# DC_DC_self_powerd.net
KiCad netlist of a schematic drawn in EAGLE
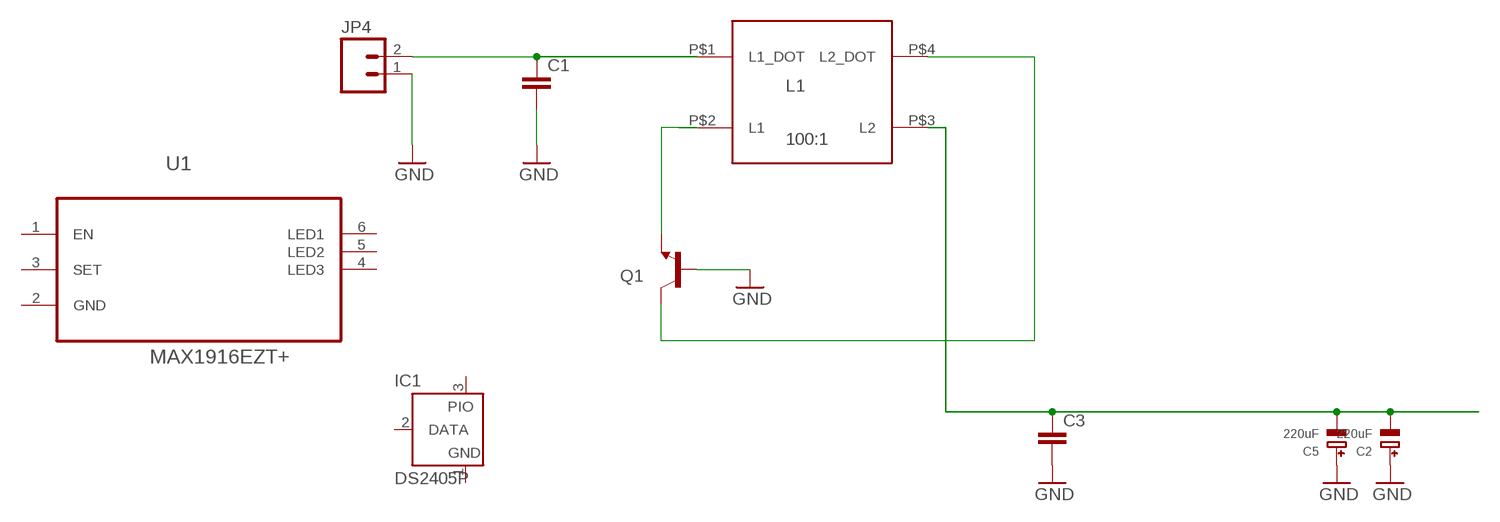
[diagram p0: schematic, sheet 1]

(export (version "E")
  (design (tool "Eeschema 10.0.6"))
  (components
    (comp (ref "C1")
      (value "CAP0805")
      (footprint "eagle-import:0805")
      (libsource (lib "eagle-import") (part "CAP0805"))
    )
    (comp (ref "C2")
      (value "220uF")
      (footprint "eagle-import:EIA7343-31_D-R")
      (libsource (lib "eagle-import") (part "CAP_TANTALUMD/7343_REFLOW"))
    )
    (comp (ref "C3")
      (value "CAP0805")
      (footprint "eagle-import:0805")
      (libsource (lib "eagle-import") (part "CAP0805"))
    )
    (comp (ref "C5")
      (value "220uF")
      (footprint "eagle-import:EIA7343-31_D-R")
      (libsource (lib "eagle-import") (part "CAP_TANTALUMD/7343_REFLOW"))
    )
    (comp (ref "IC1")
      (value "DS2405P")
      (footprint "eagle-import:TSOC6")
      (libsource (lib "eagle-import") (part "DS2405P"))
    )
    (comp (ref "JP4")
      (value "M02PTH")
      (footprint "eagle-import:1X02")
      (libsource (lib "eagle-import") (part "M02PTH"))
    )
    (comp (ref "L1")
      (value "100:1")
      (footprint "eagle-import:COILCRAFT_LPR6235")
      (libsource (lib "eagle-import") (part "COILCRAFT_LPR6235-752SML"))
    )
    (comp (ref "Q1")
      (value "TRANSISTOR_NPNSOT23-3")
      (footprint "eagle-import:SOT23-3")
      (libsource (lib "eagle-import") (part "TRANSISTOR_NPNSOT23-3"))
    )
    (comp (ref "U1")
      (value "MAX1916EZT+")
      (footprint "eagle-import:SOT95P280X110-6N")
      (libsource (lib "eagle-import") (part "MAX1916EZT+"))
    )
  )
  (nets
    (net (code "1") (name "GND") (class "Default")
      (node (ref "C1") (pin "2") (pinfunction "2_2") (pintype "passive"))
      (node (ref "C2") (pin "+") (pinfunction "+_+") (pintype "passive"))
      (node (ref "C3") (pin "2") (pinfunction "2_2") (pintype "passive"))
      (node (ref "C5") (pin "+") (pinfunction "+_+") (pintype "passive"))
      (node (ref "JP4") (pin "1") (pinfunction "1_1") (pintype "passive"))
      (node (ref "Q1") (pin "1") (pinfunction "B_1") (pintype "passive"))
    )
    (net (code "2") (name "Net-(L1-L1)") (class "Default")
      (node (ref "L1") (pin "P$2") (pinfunction "L1_P$2") (pintype "bidirectional"))
      (node (ref "Q1") (pin "2") (pinfunction "E_2") (pintype "passive"))
    )
    (net (code "3") (name "Net-(L1-L1_DOT)") (class "Default")
      (node (ref "C1") (pin "1") (pinfunction "1_1") (pintype "passive"))
      (node (ref "JP4") (pin "2") (pinfunction "2_2") (pintype "passive"))
      (node (ref "L1") (pin "P$1") (pinfunction "L1_DOT_P$1") (pintype "bidirectional"))
    )
    (net (code "4") (name "Net-(L1-L2)") (class "Default")
      (node (ref "C2") (pin "-") (pinfunction "-_-") (pintype "passive"))
      (node (ref "C3") (pin "1") (pinfunction "1_1") (pintype "passive"))
      (node (ref "C5") (pin "-") (pinfunction "-_-") (pintype "passive"))
      (node (ref "L1") (pin "P$3") (pinfunction "L2_P$3") (pintype "bidirectional"))
    )
    (net (code "5") (name "Net-(L1-L2_DOT)") (class "Default")
      (node (ref "L1") (pin "P$4") (pinfunction "L2_DOT_P$4") (pintype "bidirectional"))
      (node (ref "Q1") (pin "3") (pinfunction "C_3") (pintype "passive"))
    )
    (net (code "6") (name "unconnected-(IC1-DATA-Pad2)") (class "Default")
      (node (ref "IC1") (pin "2") (pinfunction "DATA_2") (pintype "input"))
    )
    (net (code "7") (name "unconnected-(IC1-GND-Pad1)") (class "Default")
      (node (ref "IC1") (pin "1") (pinfunction "GND_1") (pintype "passive"))
    )
    (net (code "8") (name "unconnected-(IC1-PIO-Pad3)") (class "Default")
      (node (ref "IC1") (pin "3") (pinfunction "PIO_3") (pintype "passive"))
    )
    (net (code "9") (name "unconnected-(U1-EN-Pad1)") (class "Default")
      (node (ref "U1") (pin "1") (pinfunction "EN_1") (pintype "input"))
    )
    (net (code "10") (name "unconnected-(U1-GND-Pad2)") (class "Default")
      (node (ref "U1") (pin "2") (pinfunction "GND_2") (pintype "passive"))
    )
    (net (code "11") (name "unconnected-(U1-LED1-Pad6)") (class "Default")
      (node (ref "U1") (pin "6") (pinfunction "LED1_6") (pintype "output"))
    )
    (net (code "12") (name "unconnected-(U1-LED2-Pad5)") (class "Default")
      (node (ref "U1") (pin "5") (pinfunction "LED2_5") (pintype "output"))
    )
    (net (code "13") (name "unconnected-(U1-LED3-Pad4)") (class "Default")
      (node (ref "U1") (pin "4") (pinfunction "LED3_4") (pintype "output"))
    )
    (net (code "14") (name "unconnected-(U1-SET-Pad3)") (class "Default")
      (node (ref "U1") (pin "3") (pinfunction "SET_3") (pintype "input"))
    )
  )
)
